# labwiz-module_full_breakout-0_2.net
KiCad netlist of a schematic drawn in EAGLE
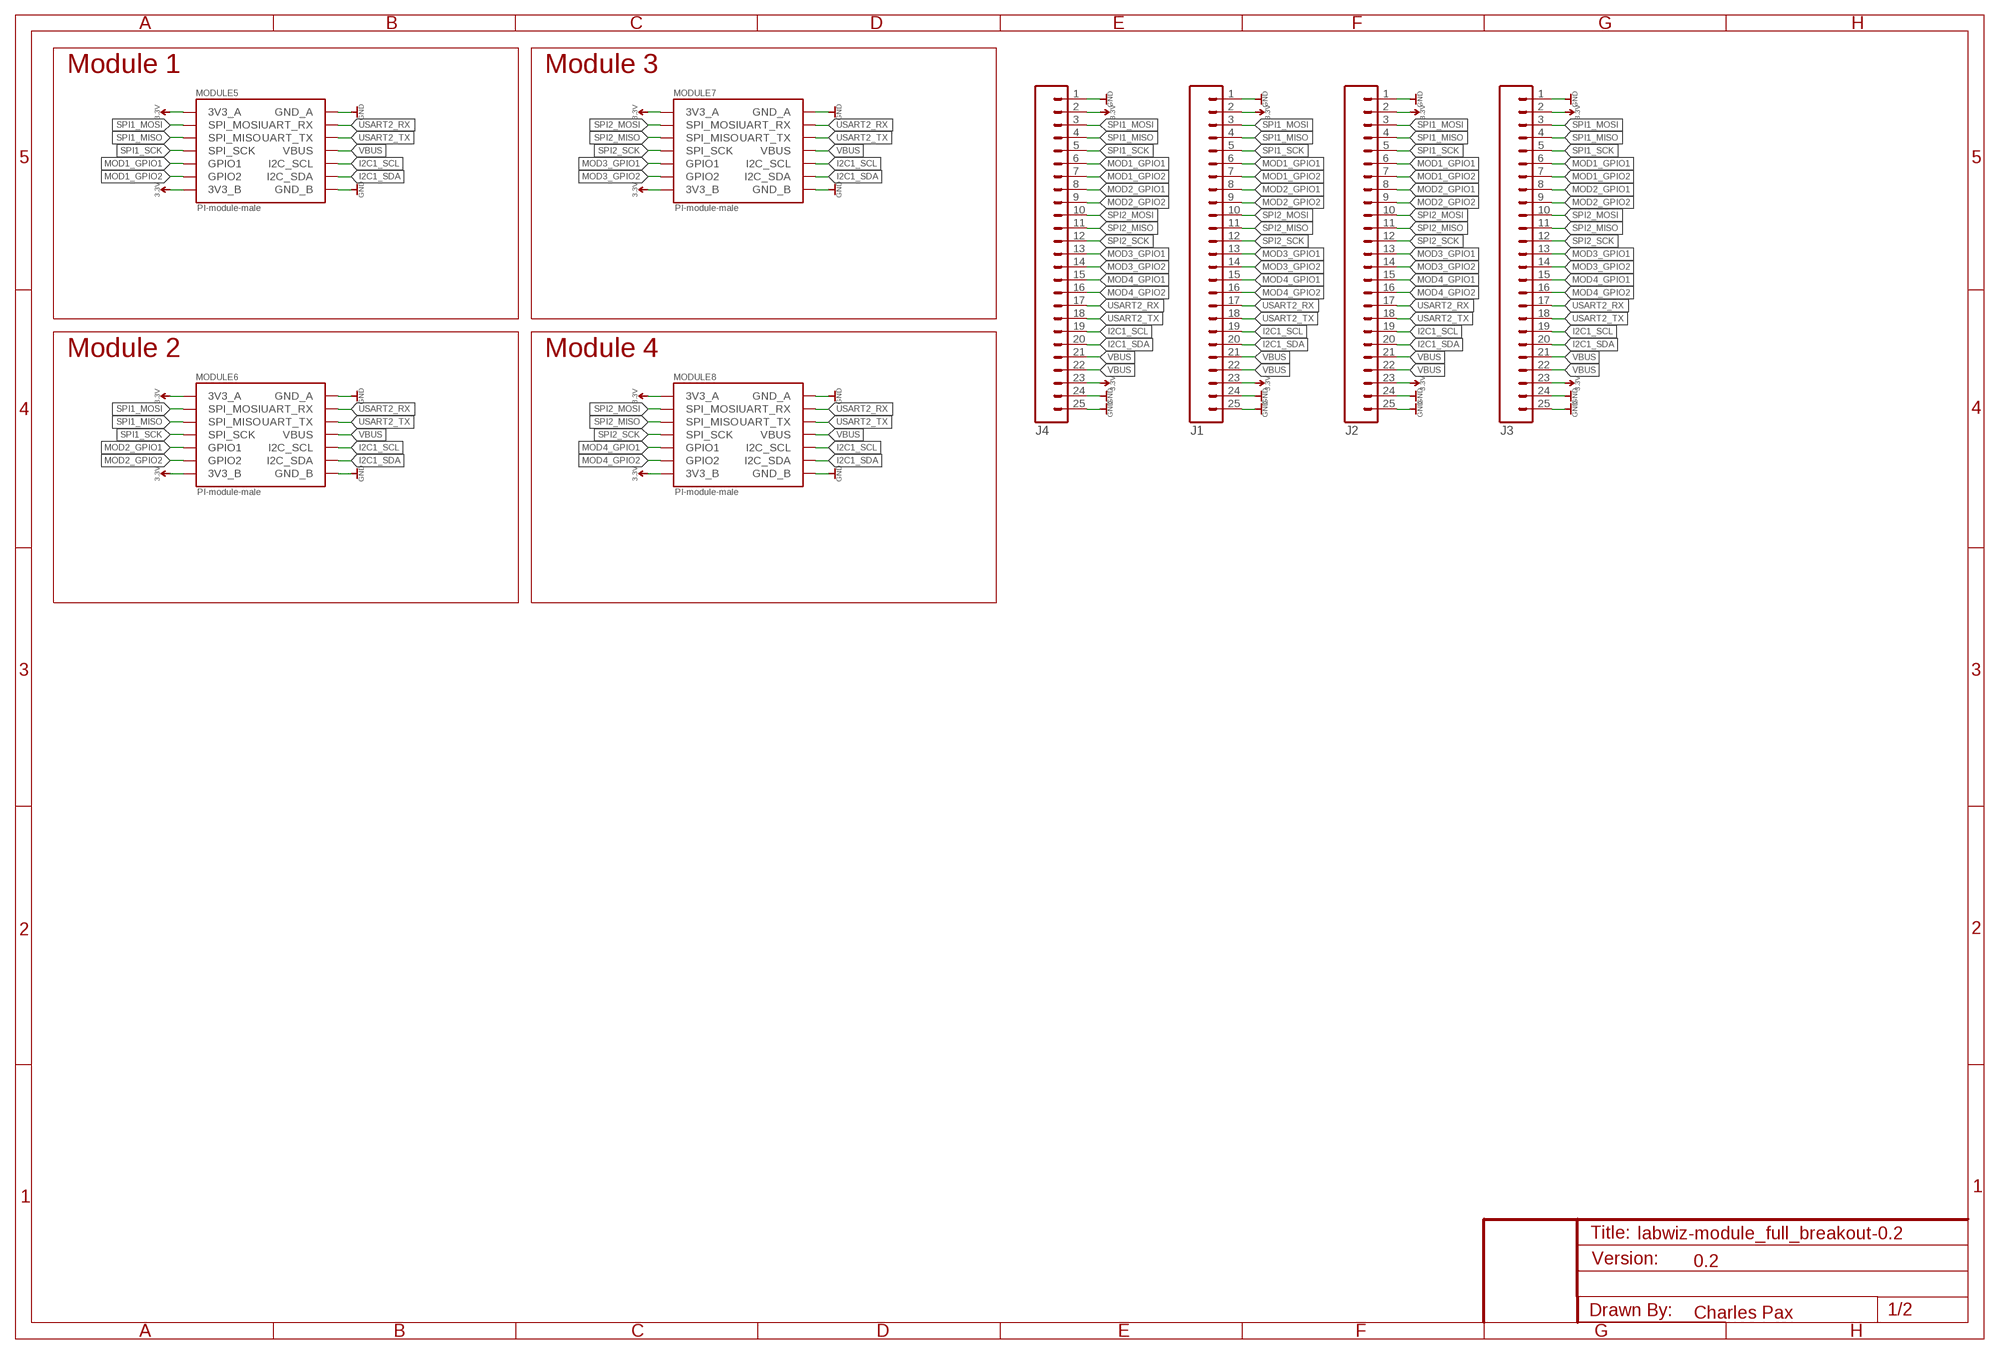
[diagram p0: schematic, sheet 1]

(export (version "E")
  (design (tool "Eeschema 10.0.6"))
  (components
    (comp (ref "J1")
      (value "M25PTH")
      (footprint "eagle-import:1X25")
      (libsource (lib "eagle-import") (part "M25PTH"))
    )
    (comp (ref "J2")
      (value "M25PTH")
      (footprint "eagle-import:1X25")
      (libsource (lib "eagle-import") (part "M25PTH"))
    )
    (comp (ref "J3")
      (value "M25PTH")
      (footprint "eagle-import:1X25")
      (libsource (lib "eagle-import") (part "M25PTH"))
    )
    (comp (ref "J4")
      (value "M25PTH")
      (footprint "eagle-import:1X25")
      (libsource (lib "eagle-import") (part "M25PTH"))
    )
    (comp (ref "MODULE5")
      (value "PI-module-male")
      (footprint "eagle-import:M07X2_2MM_EDGE")
      (fields (field (name "MF") "Pax Instruments") (field (name "MPN") "PIxxxx"))
      (libsource (lib "eagle-import") (part "PAX_MODULE_EDGE_MALE_MODULE"))
    )
    (comp (ref "MODULE6")
      (value "PI-module-male")
      (footprint "eagle-import:M07X2_2MM_EDGE")
      (fields (field (name "MF") "Pax Instruments") (field (name "MPN") "PIxxxx"))
      (libsource (lib "eagle-import") (part "PAX_MODULE_EDGE_MALE_MODULE"))
    )
    (comp (ref "MODULE7")
      (value "PI-module-male")
      (footprint "eagle-import:M07X2_2MM_EDGE")
      (fields (field (name "MF") "Pax Instruments") (field (name "MPN") "PIxxxx"))
      (libsource (lib "eagle-import") (part "PAX_MODULE_EDGE_MALE_MODULE"))
    )
    (comp (ref "MODULE8")
      (value "PI-module-male")
      (footprint "eagle-import:M07X2_2MM_EDGE")
      (fields (field (name "MF") "Pax Instruments") (field (name "MPN") "PIxxxx"))
      (libsource (lib "eagle-import") (part "PAX_MODULE_EDGE_MALE_MODULE"))
    )
  )
  (nets
    (net (code "1") (name "3.3V") (class "Default")
      (node (ref "J1") (pin "2") (pinfunction "2_2") (pintype "passive"))
      (node (ref "J1") (pin "23") (pinfunction "23_23") (pintype "passive"))
      (node (ref "J2") (pin "2") (pinfunction "2_2") (pintype "passive"))
      (node (ref "J2") (pin "23") (pinfunction "23_23") (pintype "passive"))
      (node (ref "J3") (pin "2") (pinfunction "2_2") (pintype "passive"))
      (node (ref "J3") (pin "23") (pinfunction "23_23") (pintype "passive"))
      (node (ref "J4") (pin "2") (pinfunction "2_2") (pintype "passive"))
      (node (ref "J4") (pin "23") (pinfunction "23_23") (pintype "passive"))
      (node (ref "MODULE5") (pin "P$1") (pinfunction "3V3_B_P$1") (pintype "bidirectional"))
      (node (ref "MODULE5") (pin "P$13") (pinfunction "3V3_A_P$13") (pintype "power_in"))
      (node (ref "MODULE6") (pin "P$1") (pinfunction "3V3_B_P$1") (pintype "bidirectional"))
      (node (ref "MODULE6") (pin "P$13") (pinfunction "3V3_A_P$13") (pintype "power_in"))
      (node (ref "MODULE7") (pin "P$1") (pinfunction "3V3_B_P$1") (pintype "bidirectional"))
      (node (ref "MODULE7") (pin "P$13") (pinfunction "3V3_A_P$13") (pintype "power_in"))
      (node (ref "MODULE8") (pin "P$1") (pinfunction "3V3_B_P$1") (pintype "bidirectional"))
      (node (ref "MODULE8") (pin "P$13") (pinfunction "3V3_A_P$13") (pintype "power_in"))
    )
    (net (code "2") (name "GND") (class "Default")
      (node (ref "J1") (pin "1") (pinfunction "1_1") (pintype "passive"))
      (node (ref "J1") (pin "24") (pinfunction "24_24") (pintype "passive"))
      (node (ref "J1") (pin "25") (pinfunction "25_25") (pintype "passive"))
      (node (ref "J2") (pin "1") (pinfunction "1_1") (pintype "passive"))
      (node (ref "J2") (pin "24") (pinfunction "24_24") (pintype "passive"))
      (node (ref "J2") (pin "25") (pinfunction "25_25") (pintype "passive"))
      (node (ref "J3") (pin "1") (pinfunction "1_1") (pintype "passive"))
      (node (ref "J3") (pin "24") (pinfunction "24_24") (pintype "passive"))
      (node (ref "J3") (pin "25") (pinfunction "25_25") (pintype "passive"))
      (node (ref "J4") (pin "1") (pinfunction "1_1") (pintype "passive"))
      (node (ref "J4") (pin "24") (pinfunction "24_24") (pintype "passive"))
      (node (ref "J4") (pin "25") (pinfunction "25_25") (pintype "passive"))
      (node (ref "MODULE5") (pin "P$14") (pinfunction "GND_A_P$14") (pintype "power_in"))
      (node (ref "MODULE5") (pin "P$2") (pinfunction "GND_B_P$2") (pintype "bidirectional"))
      (node (ref "MODULE6") (pin "P$14") (pinfunction "GND_A_P$14") (pintype "power_in"))
      (node (ref "MODULE6") (pin "P$2") (pinfunction "GND_B_P$2") (pintype "bidirectional"))
      (node (ref "MODULE7") (pin "P$14") (pinfunction "GND_A_P$14") (pintype "power_in"))
      (node (ref "MODULE7") (pin "P$2") (pinfunction "GND_B_P$2") (pintype "bidirectional"))
      (node (ref "MODULE8") (pin "P$14") (pinfunction "GND_A_P$14") (pintype "power_in"))
      (node (ref "MODULE8") (pin "P$2") (pinfunction "GND_B_P$2") (pintype "bidirectional"))
    )
    (net (code "3") (name "I2C1_SCL") (class "Default")
      (node (ref "J1") (pin "19") (pinfunction "19_19") (pintype "passive"))
      (node (ref "J2") (pin "19") (pinfunction "19_19") (pintype "passive"))
      (node (ref "J3") (pin "19") (pinfunction "19_19") (pintype "passive"))
      (node (ref "J4") (pin "19") (pinfunction "19_19") (pintype "passive"))
      (node (ref "MODULE5") (pin "P$6") (pinfunction "I2C_SCL_P$6") (pintype "bidirectional"))
      (node (ref "MODULE6") (pin "P$6") (pinfunction "I2C_SCL_P$6") (pintype "bidirectional"))
      (node (ref "MODULE7") (pin "P$6") (pinfunction "I2C_SCL_P$6") (pintype "bidirectional"))
      (node (ref "MODULE8") (pin "P$6") (pinfunction "I2C_SCL_P$6") (pintype "bidirectional"))
    )
    (net (code "4") (name "I2C1_SDA") (class "Default")
      (node (ref "J1") (pin "20") (pinfunction "20_20") (pintype "passive"))
      (node (ref "J2") (pin "20") (pinfunction "20_20") (pintype "passive"))
      (node (ref "J3") (pin "20") (pinfunction "20_20") (pintype "passive"))
      (node (ref "J4") (pin "20") (pinfunction "20_20") (pintype "passive"))
      (node (ref "MODULE5") (pin "P$4") (pinfunction "I2C_SDA_P$4") (pintype "bidirectional"))
      (node (ref "MODULE6") (pin "P$4") (pinfunction "I2C_SDA_P$4") (pintype "bidirectional"))
      (node (ref "MODULE7") (pin "P$4") (pinfunction "I2C_SDA_P$4") (pintype "bidirectional"))
      (node (ref "MODULE8") (pin "P$4") (pinfunction "I2C_SDA_P$4") (pintype "bidirectional"))
    )
    (net (code "5") (name "MOD1_GPIO1") (class "Default")
      (node (ref "J1") (pin "6") (pinfunction "6_6") (pintype "passive"))
      (node (ref "J2") (pin "6") (pinfunction "6_6") (pintype "passive"))
      (node (ref "J3") (pin "6") (pinfunction "6_6") (pintype "passive"))
      (node (ref "J4") (pin "6") (pinfunction "6_6") (pintype "passive"))
      (node (ref "MODULE5") (pin "P$5") (pinfunction "GPIO1_P$5") (pintype "bidirectional"))
    )
    (net (code "6") (name "MOD1_GPIO2") (class "Default")
      (node (ref "J1") (pin "7") (pinfunction "7_7") (pintype "passive"))
      (node (ref "J2") (pin "7") (pinfunction "7_7") (pintype "passive"))
      (node (ref "J3") (pin "7") (pinfunction "7_7") (pintype "passive"))
      (node (ref "J4") (pin "7") (pinfunction "7_7") (pintype "passive"))
      (node (ref "MODULE5") (pin "P$3") (pinfunction "GPIO2_P$3") (pintype "bidirectional"))
    )
    (net (code "7") (name "MOD2_GPIO1") (class "Default")
      (node (ref "J1") (pin "8") (pinfunction "8_8") (pintype "passive"))
      (node (ref "J2") (pin "8") (pinfunction "8_8") (pintype "passive"))
      (node (ref "J3") (pin "8") (pinfunction "8_8") (pintype "passive"))
      (node (ref "J4") (pin "8") (pinfunction "8_8") (pintype "passive"))
      (node (ref "MODULE6") (pin "P$5") (pinfunction "GPIO1_P$5") (pintype "bidirectional"))
    )
    (net (code "8") (name "MOD2_GPIO2") (class "Default")
      (node (ref "J1") (pin "9") (pinfunction "9_9") (pintype "passive"))
      (node (ref "J2") (pin "9") (pinfunction "9_9") (pintype "passive"))
      (node (ref "J3") (pin "9") (pinfunction "9_9") (pintype "passive"))
      (node (ref "J4") (pin "9") (pinfunction "9_9") (pintype "passive"))
      (node (ref "MODULE6") (pin "P$3") (pinfunction "GPIO2_P$3") (pintype "bidirectional"))
    )
    (net (code "9") (name "MOD3_GPIO1") (class "Default")
      (node (ref "J1") (pin "13") (pinfunction "13_13") (pintype "passive"))
      (node (ref "J2") (pin "13") (pinfunction "13_13") (pintype "passive"))
      (node (ref "J3") (pin "13") (pinfunction "13_13") (pintype "passive"))
      (node (ref "J4") (pin "13") (pinfunction "13_13") (pintype "passive"))
      (node (ref "MODULE7") (pin "P$5") (pinfunction "GPIO1_P$5") (pintype "bidirectional"))
    )
    (net (code "10") (name "MOD3_GPIO2") (class "Default")
      (node (ref "J1") (pin "14") (pinfunction "14_14") (pintype "passive"))
      (node (ref "J2") (pin "14") (pinfunction "14_14") (pintype "passive"))
      (node (ref "J3") (pin "14") (pinfunction "14_14") (pintype "passive"))
      (node (ref "J4") (pin "14") (pinfunction "14_14") (pintype "passive"))
      (node (ref "MODULE7") (pin "P$3") (pinfunction "GPIO2_P$3") (pintype "bidirectional"))
    )
    (net (code "11") (name "MOD4_GPIO1") (class "Default")
      (node (ref "J1") (pin "15") (pinfunction "15_15") (pintype "passive"))
      (node (ref "J2") (pin "15") (pinfunction "15_15") (pintype "passive"))
      (node (ref "J3") (pin "15") (pinfunction "15_15") (pintype "passive"))
      (node (ref "J4") (pin "15") (pinfunction "15_15") (pintype "passive"))
      (node (ref "MODULE8") (pin "P$5") (pinfunction "GPIO1_P$5") (pintype "bidirectional"))
    )
    (net (code "12") (name "MOD4_GPIO2") (class "Default")
      (node (ref "J1") (pin "16") (pinfunction "16_16") (pintype "passive"))
      (node (ref "J2") (pin "16") (pinfunction "16_16") (pintype "passive"))
      (node (ref "J3") (pin "16") (pinfunction "16_16") (pintype "passive"))
      (node (ref "J4") (pin "16") (pinfunction "16_16") (pintype "passive"))
      (node (ref "MODULE8") (pin "P$3") (pinfunction "GPIO2_P$3") (pintype "bidirectional"))
    )
    (net (code "13") (name "SPI1_MISO") (class "Default")
      (node (ref "J1") (pin "4") (pinfunction "4_4") (pintype "passive"))
      (node (ref "J2") (pin "4") (pinfunction "4_4") (pintype "passive"))
      (node (ref "J3") (pin "4") (pinfunction "4_4") (pintype "passive"))
      (node (ref "J4") (pin "4") (pinfunction "4_4") (pintype "passive"))
      (node (ref "MODULE5") (pin "P$9") (pinfunction "SPI_MISO_P$9") (pintype "bidirectional"))
      (node (ref "MODULE6") (pin "P$9") (pinfunction "SPI_MISO_P$9") (pintype "bidirectional"))
    )
    (net (code "14") (name "SPI1_MOSI") (class "Default")
      (node (ref "J1") (pin "3") (pinfunction "3_3") (pintype "passive"))
      (node (ref "J2") (pin "3") (pinfunction "3_3") (pintype "passive"))
      (node (ref "J3") (pin "3") (pinfunction "3_3") (pintype "passive"))
      (node (ref "J4") (pin "3") (pinfunction "3_3") (pintype "passive"))
      (node (ref "MODULE5") (pin "P$11") (pinfunction "SPI_MOSI_P$11") (pintype "bidirectional"))
      (node (ref "MODULE6") (pin "P$11") (pinfunction "SPI_MOSI_P$11") (pintype "bidirectional"))
    )
    (net (code "15") (name "SPI1_SCK") (class "Default")
      (node (ref "J1") (pin "5") (pinfunction "5_5") (pintype "passive"))
      (node (ref "J2") (pin "5") (pinfunction "5_5") (pintype "passive"))
      (node (ref "J3") (pin "5") (pinfunction "5_5") (pintype "passive"))
      (node (ref "J4") (pin "5") (pinfunction "5_5") (pintype "passive"))
      (node (ref "MODULE5") (pin "P$7") (pinfunction "SPI_SCK_P$7") (pintype "bidirectional"))
      (node (ref "MODULE6") (pin "P$7") (pinfunction "SPI_SCK_P$7") (pintype "bidirectional"))
    )
    (net (code "16") (name "SPI2_MISO") (class "Default")
      (node (ref "J1") (pin "11") (pinfunction "11_11") (pintype "passive"))
      (node (ref "J2") (pin "11") (pinfunction "11_11") (pintype "passive"))
      (node (ref "J3") (pin "11") (pinfunction "11_11") (pintype "passive"))
      (node (ref "J4") (pin "11") (pinfunction "11_11") (pintype "passive"))
      (node (ref "MODULE7") (pin "P$9") (pinfunction "SPI_MISO_P$9") (pintype "bidirectional"))
      (node (ref "MODULE8") (pin "P$9") (pinfunction "SPI_MISO_P$9") (pintype "bidirectional"))
    )
    (net (code "17") (name "SPI2_MOSI") (class "Default")
      (node (ref "J1") (pin "10") (pinfunction "10_10") (pintype "passive"))
      (node (ref "J2") (pin "10") (pinfunction "10_10") (pintype "passive"))
      (node (ref "J3") (pin "10") (pinfunction "10_10") (pintype "passive"))
      (node (ref "J4") (pin "10") (pinfunction "10_10") (pintype "passive"))
      (node (ref "MODULE7") (pin "P$11") (pinfunction "SPI_MOSI_P$11") (pintype "bidirectional"))
      (node (ref "MODULE8") (pin "P$11") (pinfunction "SPI_MOSI_P$11") (pintype "bidirectional"))
    )
    (net (code "18") (name "SPI2_SCK") (class "Default")
      (node (ref "J1") (pin "12") (pinfunction "12_12") (pintype "passive"))
      (node (ref "J2") (pin "12") (pinfunction "12_12") (pintype "passive"))
      (node (ref "J3") (pin "12") (pinfunction "12_12") (pintype "passive"))
      (node (ref "J4") (pin "12") (pinfunction "12_12") (pintype "passive"))
      (node (ref "MODULE7") (pin "P$7") (pinfunction "SPI_SCK_P$7") (pintype "bidirectional"))
      (node (ref "MODULE8") (pin "P$7") (pinfunction "SPI_SCK_P$7") (pintype "bidirectional"))
    )
    (net (code "19") (name "USART2_RX") (class "Default")
      (node (ref "J1") (pin "17") (pinfunction "17_17") (pintype "passive"))
      (node (ref "J2") (pin "17") (pinfunction "17_17") (pintype "passive"))
      (node (ref "J3") (pin "17") (pinfunction "17_17") (pintype "passive"))
      (node (ref "J4") (pin "17") (pinfunction "17_17") (pintype "passive"))
      (node (ref "MODULE5") (pin "P$12") (pinfunction "UART_RX_P$12") (pintype "bidirectional"))
      (node (ref "MODULE6") (pin "P$12") (pinfunction "UART_RX_P$12") (pintype "bidirectional"))
      (node (ref "MODULE7") (pin "P$12") (pinfunction "UART_RX_P$12") (pintype "bidirectional"))
      (node (ref "MODULE8") (pin "P$12") (pinfunction "UART_RX_P$12") (pintype "bidirectional"))
    )
    (net (code "20") (name "USART2_TX") (class "Default")
      (node (ref "J1") (pin "18") (pinfunction "18_18") (pintype "passive"))
      (node (ref "J2") (pin "18") (pinfunction "18_18") (pintype "passive"))
      (node (ref "J3") (pin "18") (pinfunction "18_18") (pintype "passive"))
      (node (ref "J4") (pin "18") (pinfunction "18_18") (pintype "passive"))
      (node (ref "MODULE5") (pin "P$10") (pinfunction "UART_TX_P$10") (pintype "bidirectional"))
      (node (ref "MODULE6") (pin "P$10") (pinfunction "UART_TX_P$10") (pintype "bidirectional"))
      (node (ref "MODULE7") (pin "P$10") (pinfunction "UART_TX_P$10") (pintype "bidirectional"))
      (node (ref "MODULE8") (pin "P$10") (pinfunction "UART_TX_P$10") (pintype "bidirectional"))
    )
    (net (code "21") (name "VBUS") (class "Default")
      (node (ref "J1") (pin "21") (pinfunction "21_21") (pintype "passive"))
      (node (ref "J1") (pin "22") (pinfunction "22_22") (pintype "passive"))
      (node (ref "J2") (pin "21") (pinfunction "21_21") (pintype "passive"))
      (node (ref "J2") (pin "22") (pinfunction "22_22") (pintype "passive"))
      (node (ref "J3") (pin "21") (pinfunction "21_21") (pintype "passive"))
      (node (ref "J3") (pin "22") (pinfunction "22_22") (pintype "passive"))
      (node (ref "J4") (pin "21") (pinfunction "21_21") (pintype "passive"))
      (node (ref "J4") (pin "22") (pinfunction "22_22") (pintype "passive"))
      (node (ref "MODULE5") (pin "P$8") (pinfunction "VBUS_P$8") (pintype "bidirectional"))
      (node (ref "MODULE6") (pin "P$8") (pinfunction "VBUS_P$8") (pintype "bidirectional"))
      (node (ref "MODULE7") (pin "P$8") (pinfunction "VBUS_P$8") (pintype "bidirectional"))
      (node (ref "MODULE8") (pin "P$8") (pinfunction "VBUS_P$8") (pintype "bidirectional"))
    )
  )
)
